# 2_ESP_batt_shield-MCU_and_sensors.net
KiCad netlist of a schematic drawn in Altium Designer
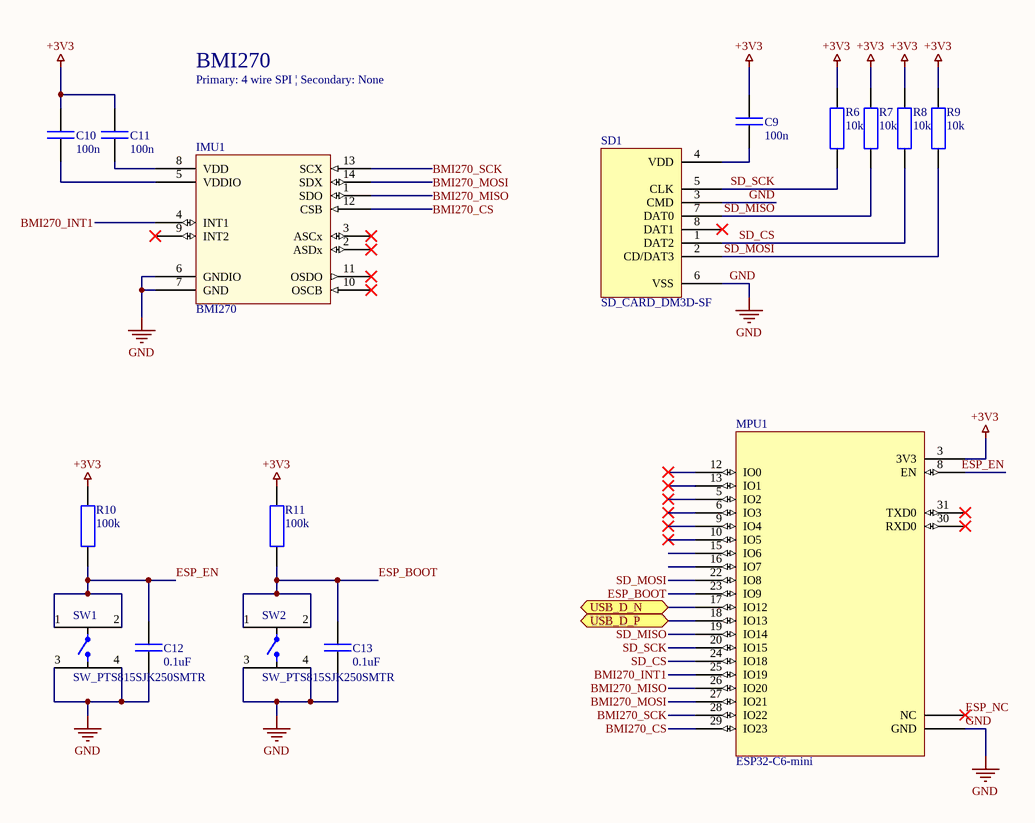
[diagram p0: 2_ESP_batt_shield-MCU_and_sensors.SchDoc]

(export (version "E")
  (design (tool "Eeschema 10.0.6"))
  (components
    (comp (ref "C9")
      (value "100n")
      (footprint "CAP_0603")
      (libsource (lib "moma_altium_library") (part "CAP_0603"))
    )
    (comp (ref "C10")
      (value "100n")
      (footprint "CAP_0603")
      (libsource (lib "moma_altium_library") (part "CAP_0603"))
    )
    (comp (ref "C11")
      (value "100n")
      (footprint "CAP_0603")
      (libsource (lib "moma_altium_library") (part "CAP_0603"))
    )
    (comp (ref "C12")
      (value "0.1uF")
      (footprint "CAP_0603")
      (libsource (lib "moma_altium_library") (part "CAP_0603"))
    )
    (comp (ref "C13")
      (value "0.1uF")
      (footprint "CAP_0603")
      (libsource (lib "moma_altium_library") (part "CAP_0603"))
    )
    (comp (ref "IMU1")
      (value "BMI270")
      (footprint "LGA14_3x2.5x0.8mm")
      (libsource (lib "moma_altium_library") (part "BMI270"))
    )
    (comp (ref "MPU1")
      (value "ESP32-C6-mini")
      (footprint "ESP32C6_MINI")
      (libsource (lib "moma_altium_library") (part "ESP32-C6-mini"))
    )
    (comp (ref "R6")
      (value "10k")
      (footprint "RES_0603")
      (libsource (lib "moma_altium_library") (part "RES_0603"))
    )
    (comp (ref "R7")
      (value "10k")
      (footprint "RES_0603")
      (libsource (lib "moma_altium_library") (part "RES_0603"))
    )
    (comp (ref "R8")
      (value "10k")
      (footprint "RES_0603")
      (libsource (lib "moma_altium_library") (part "RES_0603"))
    )
    (comp (ref "R9")
      (value "10k")
      (footprint "RES_0603")
      (libsource (lib "moma_altium_library") (part "RES_0603"))
    )
    (comp (ref "R10")
      (value "100k")
      (footprint "RES_0603")
      (libsource (lib "moma_altium_library") (part "RES_0603"))
    )
    (comp (ref "R11")
      (value "100k")
      (footprint "RES_0603")
      (libsource (lib "moma_altium_library") (part "RES_0603"))
    )
    (comp (ref "SD1")
      (value "SD_CARD_DM3D-SF")
      (footprint "SD_DM3D-SF")
      (libsource (lib "moma_altium_library") (part "SD_CARD_DM3D-SF"))
    )
    (comp (ref "SW1")
      (value "SW_PTS815SJK250SMTR")
      (footprint "PTS815SJK250SMTR")
      (libsource (lib "moma_altium_library") (part "SW_PTS815SJK250SMTR"))
    )
    (comp (ref "SW2")
      (value "SW_PTS815SJK250SMTR")
      (footprint "PTS815SJK250SMTR")
      (libsource (lib "moma_altium_library") (part "SW_PTS815SJK250SMTR"))
    )
  )
  (nets
    (net (code "1") (name "+3V3") (class "Default")
      (node (ref "C10") (pin "2") (pinfunction "2_2") (pintype "passive"))
      (node (ref "C11") (pin "2") (pinfunction "2_2") (pintype "passive"))
      (node (ref "C9") (pin "2") (pinfunction "2_2") (pintype "passive"))
      (node (ref "MPU1") (pin "3") (pinfunction "3V3_3") (pintype "power_in"))
      (node (ref "R10") (pin "2") (pinfunction "2_2") (pintype "passive"))
      (node (ref "R11") (pin "2") (pinfunction "2_2") (pintype "passive"))
      (node (ref "R6") (pin "2") (pinfunction "2_2") (pintype "passive"))
      (node (ref "R7") (pin "2") (pinfunction "2_2") (pintype "passive"))
      (node (ref "R8") (pin "2") (pinfunction "2_2") (pintype "passive"))
      (node (ref "R9") (pin "2") (pinfunction "2_2") (pintype "passive"))
    )
    (net (code "2") (name "/BMI270_CS") (class "Default")
      (node (ref "IMU1") (pin "12") (pinfunction "CSB_12") (pintype "input"))
      (node (ref "MPU1") (pin "29") (pinfunction "IO23_29") (pintype "bidirectional"))
    )
    (net (code "3") (name "/BMI270_INT1") (class "Default")
      (node (ref "IMU1") (pin "4") (pinfunction "INT1_4") (pintype "bidirectional"))
      (node (ref "MPU1") (pin "25") (pinfunction "IO19_25") (pintype "bidirectional"))
    )
    (net (code "4") (name "/BMI270_MISO") (class "Default")
      (node (ref "IMU1") (pin "1") (pinfunction "SDO_1") (pintype "bidirectional"))
      (node (ref "MPU1") (pin "26") (pinfunction "IO20_26") (pintype "bidirectional"))
    )
    (net (code "5") (name "/BMI270_MOSI") (class "Default")
      (node (ref "IMU1") (pin "14") (pinfunction "SDX_14") (pintype "bidirectional"))
      (node (ref "MPU1") (pin "27") (pinfunction "IO21_27") (pintype "bidirectional"))
    )
    (net (code "6") (name "/BMI270_SCK") (class "Default")
      (node (ref "IMU1") (pin "13") (pinfunction "SCX_13") (pintype "input"))
      (node (ref "MPU1") (pin "28") (pinfunction "IO22_28") (pintype "bidirectional"))
    )
    (net (code "7") (name "/ESP_BOOT") (class "Default")
      (node (ref "C13") (pin "2") (pinfunction "2_2") (pintype "passive"))
      (node (ref "MPU1") (pin "23") (pinfunction "IO9_23") (pintype "bidirectional"))
      (node (ref "R11") (pin "1") (pinfunction "1_1") (pintype "passive"))
      (node (ref "SW2") (pin "1") (pinfunction "1_1") (pintype "passive"))
      (node (ref "SW2") (pin "2") (pinfunction "2_2") (pintype "passive"))
    )
    (net (code "8") (name "/ESP_EN") (class "Default")
      (node (ref "C12") (pin "2") (pinfunction "2_2") (pintype "passive"))
      (node (ref "MPU1") (pin "8") (pinfunction "EN_8") (pintype "bidirectional"))
      (node (ref "R10") (pin "1") (pinfunction "1_1") (pintype "passive"))
      (node (ref "SW1") (pin "1") (pinfunction "1_1") (pintype "passive"))
      (node (ref "SW1") (pin "2") (pinfunction "2_2") (pintype "passive"))
    )
    (net (code "9") (name "/ESP_NC") (class "Default")
      (node (ref "MPU1") (pin "7") (pinfunction "NC_7") (pintype "passive+no_connect"))
    )
    (net (code "10") (name "/SD_CS") (class "Default")
      (node (ref "MPU1") (pin "24") (pinfunction "IO18_24") (pintype "bidirectional"))
      (node (ref "R8") (pin "1") (pinfunction "1_1") (pintype "passive"))
      (node (ref "SD1") (pin "1") (pinfunction "DAT2_1") (pintype "passive"))
    )
    (net (code "11") (name "/SD_MISO") (class "Default")
      (node (ref "MPU1") (pin "19") (pinfunction "IO14_19") (pintype "bidirectional"))
      (node (ref "R7") (pin "1") (pinfunction "1_1") (pintype "passive"))
      (node (ref "SD1") (pin "7") (pinfunction "DAT0_7") (pintype "passive"))
    )
    (net (code "12") (name "/SD_MOSI") (class "Default")
      (node (ref "MPU1") (pin "22") (pinfunction "IO8_22") (pintype "bidirectional"))
      (node (ref "R9") (pin "1") (pinfunction "1_1") (pintype "passive"))
      (node (ref "SD1") (pin "2") (pinfunction "CD/DAT3_2") (pintype "passive"))
    )
    (net (code "13") (name "/SD_SCK") (class "Default")
      (node (ref "MPU1") (pin "20") (pinfunction "IO15_20") (pintype "bidirectional"))
      (node (ref "R6") (pin "1") (pinfunction "1_1") (pintype "passive"))
      (node (ref "SD1") (pin "5") (pinfunction "CLK_5") (pintype "passive"))
    )
    (net (code "14") (name "/USB_D_N") (class "Default")
      (node (ref "MPU1") (pin "17") (pinfunction "IO12_17") (pintype "bidirectional"))
    )
    (net (code "15") (name "/USB_D_P") (class "Default")
      (node (ref "MPU1") (pin "18") (pinfunction "IO13_18") (pintype "bidirectional"))
    )
    (net (code "16") (name "GND") (class "Default")
      (node (ref "C12") (pin "1") (pinfunction "1_1") (pintype "passive"))
      (node (ref "C13") (pin "1") (pinfunction "1_1") (pintype "passive"))
      (node (ref "IMU1") (pin "6") (pinfunction "GNDIO_6") (pintype "power_in"))
      (node (ref "IMU1") (pin "7") (pinfunction "GND_7") (pintype "power_in"))
      (node (ref "MPU1") (pin "1") (pinfunction "GND_1") (pintype "power_in"))
      (node (ref "SD1") (pin "3") (pinfunction "CMD_3") (pintype "passive"))
      (node (ref "SD1") (pin "6") (pinfunction "VSS_6") (pintype "passive"))
      (node (ref "SW1") (pin "3") (pinfunction "3_3") (pintype "passive"))
      (node (ref "SW1") (pin "4") (pinfunction "4_4") (pintype "passive"))
      (node (ref "SW2") (pin "3") (pinfunction "3_3") (pintype "passive"))
      (node (ref "SW2") (pin "4") (pinfunction "4_4") (pintype "passive"))
    )
    (net (code "17") (name "Net-(IMU1-VDD)") (class "Default")
      (node (ref "C11") (pin "1") (pinfunction "1_1") (pintype "passive"))
      (node (ref "IMU1") (pin "8") (pinfunction "VDD_8") (pintype "power_in"))
    )
    (net (code "18") (name "Net-(IMU1-VDDIO)") (class "Default")
      (node (ref "C10") (pin "1") (pinfunction "1_1") (pintype "passive"))
      (node (ref "IMU1") (pin "5") (pinfunction "VDDIO_5") (pintype "power_in"))
    )
    (net (code "19") (name "Net-(SD1-VDD)") (class "Default")
      (node (ref "C9") (pin "1") (pinfunction "1_1") (pintype "passive"))
      (node (ref "SD1") (pin "4") (pinfunction "VDD_4") (pintype "passive"))
    )
    (net (code "20") (name "unconnected-(IMU1-ASCx-Pad3)") (class "Default")
      (node (ref "IMU1") (pin "3") (pinfunction "ASCx_3") (pintype "bidirectional+no_connect"))
    )
    (net (code "21") (name "unconnected-(IMU1-ASDx-Pad2)") (class "Default")
      (node (ref "IMU1") (pin "2") (pinfunction "ASDx_2") (pintype "bidirectional+no_connect"))
    )
    (net (code "22") (name "unconnected-(IMU1-INT2-Pad9)") (class "Default")
      (node (ref "IMU1") (pin "9") (pinfunction "INT2_9") (pintype "bidirectional+no_connect"))
    )
    (net (code "23") (name "unconnected-(IMU1-OSCB-Pad10)") (class "Default")
      (node (ref "IMU1") (pin "10") (pinfunction "OSCB_10") (pintype "input+no_connect"))
    )
    (net (code "24") (name "unconnected-(IMU1-OSDO-Pad11)") (class "Default")
      (node (ref "IMU1") (pin "11") (pinfunction "OSDO_11") (pintype "output+no_connect"))
    )
    (net (code "25") (name "unconnected-(MPU1-IO0-Pad12)") (class "Default")
      (node (ref "MPU1") (pin "12") (pinfunction "IO0_12") (pintype "bidirectional+no_connect"))
    )
    (net (code "26") (name "unconnected-(MPU1-IO1-Pad13)") (class "Default")
      (node (ref "MPU1") (pin "13") (pinfunction "IO1_13") (pintype "bidirectional+no_connect"))
    )
    (net (code "27") (name "unconnected-(MPU1-IO2-Pad5)") (class "Default")
      (node (ref "MPU1") (pin "5") (pinfunction "IO2_5") (pintype "bidirectional+no_connect"))
    )
    (net (code "28") (name "unconnected-(MPU1-IO3-Pad6)") (class "Default")
      (node (ref "MPU1") (pin "6") (pinfunction "IO3_6") (pintype "bidirectional+no_connect"))
    )
    (net (code "29") (name "unconnected-(MPU1-IO4-Pad9)") (class "Default")
      (node (ref "MPU1") (pin "9") (pinfunction "IO4_9") (pintype "bidirectional+no_connect"))
    )
    (net (code "30") (name "unconnected-(MPU1-IO5-Pad10)") (class "Default")
      (node (ref "MPU1") (pin "10") (pinfunction "IO5_10") (pintype "bidirectional+no_connect"))
    )
    (net (code "31") (name "unconnected-(MPU1-IO6-Pad15)") (class "Default")
      (node (ref "MPU1") (pin "15") (pinfunction "IO6_15") (pintype "bidirectional"))
    )
    (net (code "32") (name "unconnected-(MPU1-IO7-Pad16)") (class "Default")
      (node (ref "MPU1") (pin "16") (pinfunction "IO7_16") (pintype "bidirectional"))
    )
    (net (code "33") (name "unconnected-(MPU1-RXD0-Pad30)") (class "Default")
      (node (ref "MPU1") (pin "30") (pinfunction "RXD0_30") (pintype "bidirectional+no_connect"))
    )
    (net (code "34") (name "unconnected-(MPU1-TXD0-Pad31)") (class "Default")
      (node (ref "MPU1") (pin "31") (pinfunction "TXD0_31") (pintype "bidirectional+no_connect"))
    )
    (net (code "35") (name "unconnected-(SD1-DAT1-Pad8)") (class "Default")
      (node (ref "SD1") (pin "8") (pinfunction "DAT1_8") (pintype "passive+no_connect"))
    )
  )
)
